# backplane_v1_0.net
KiCad netlist of a schematic drawn in EAGLE
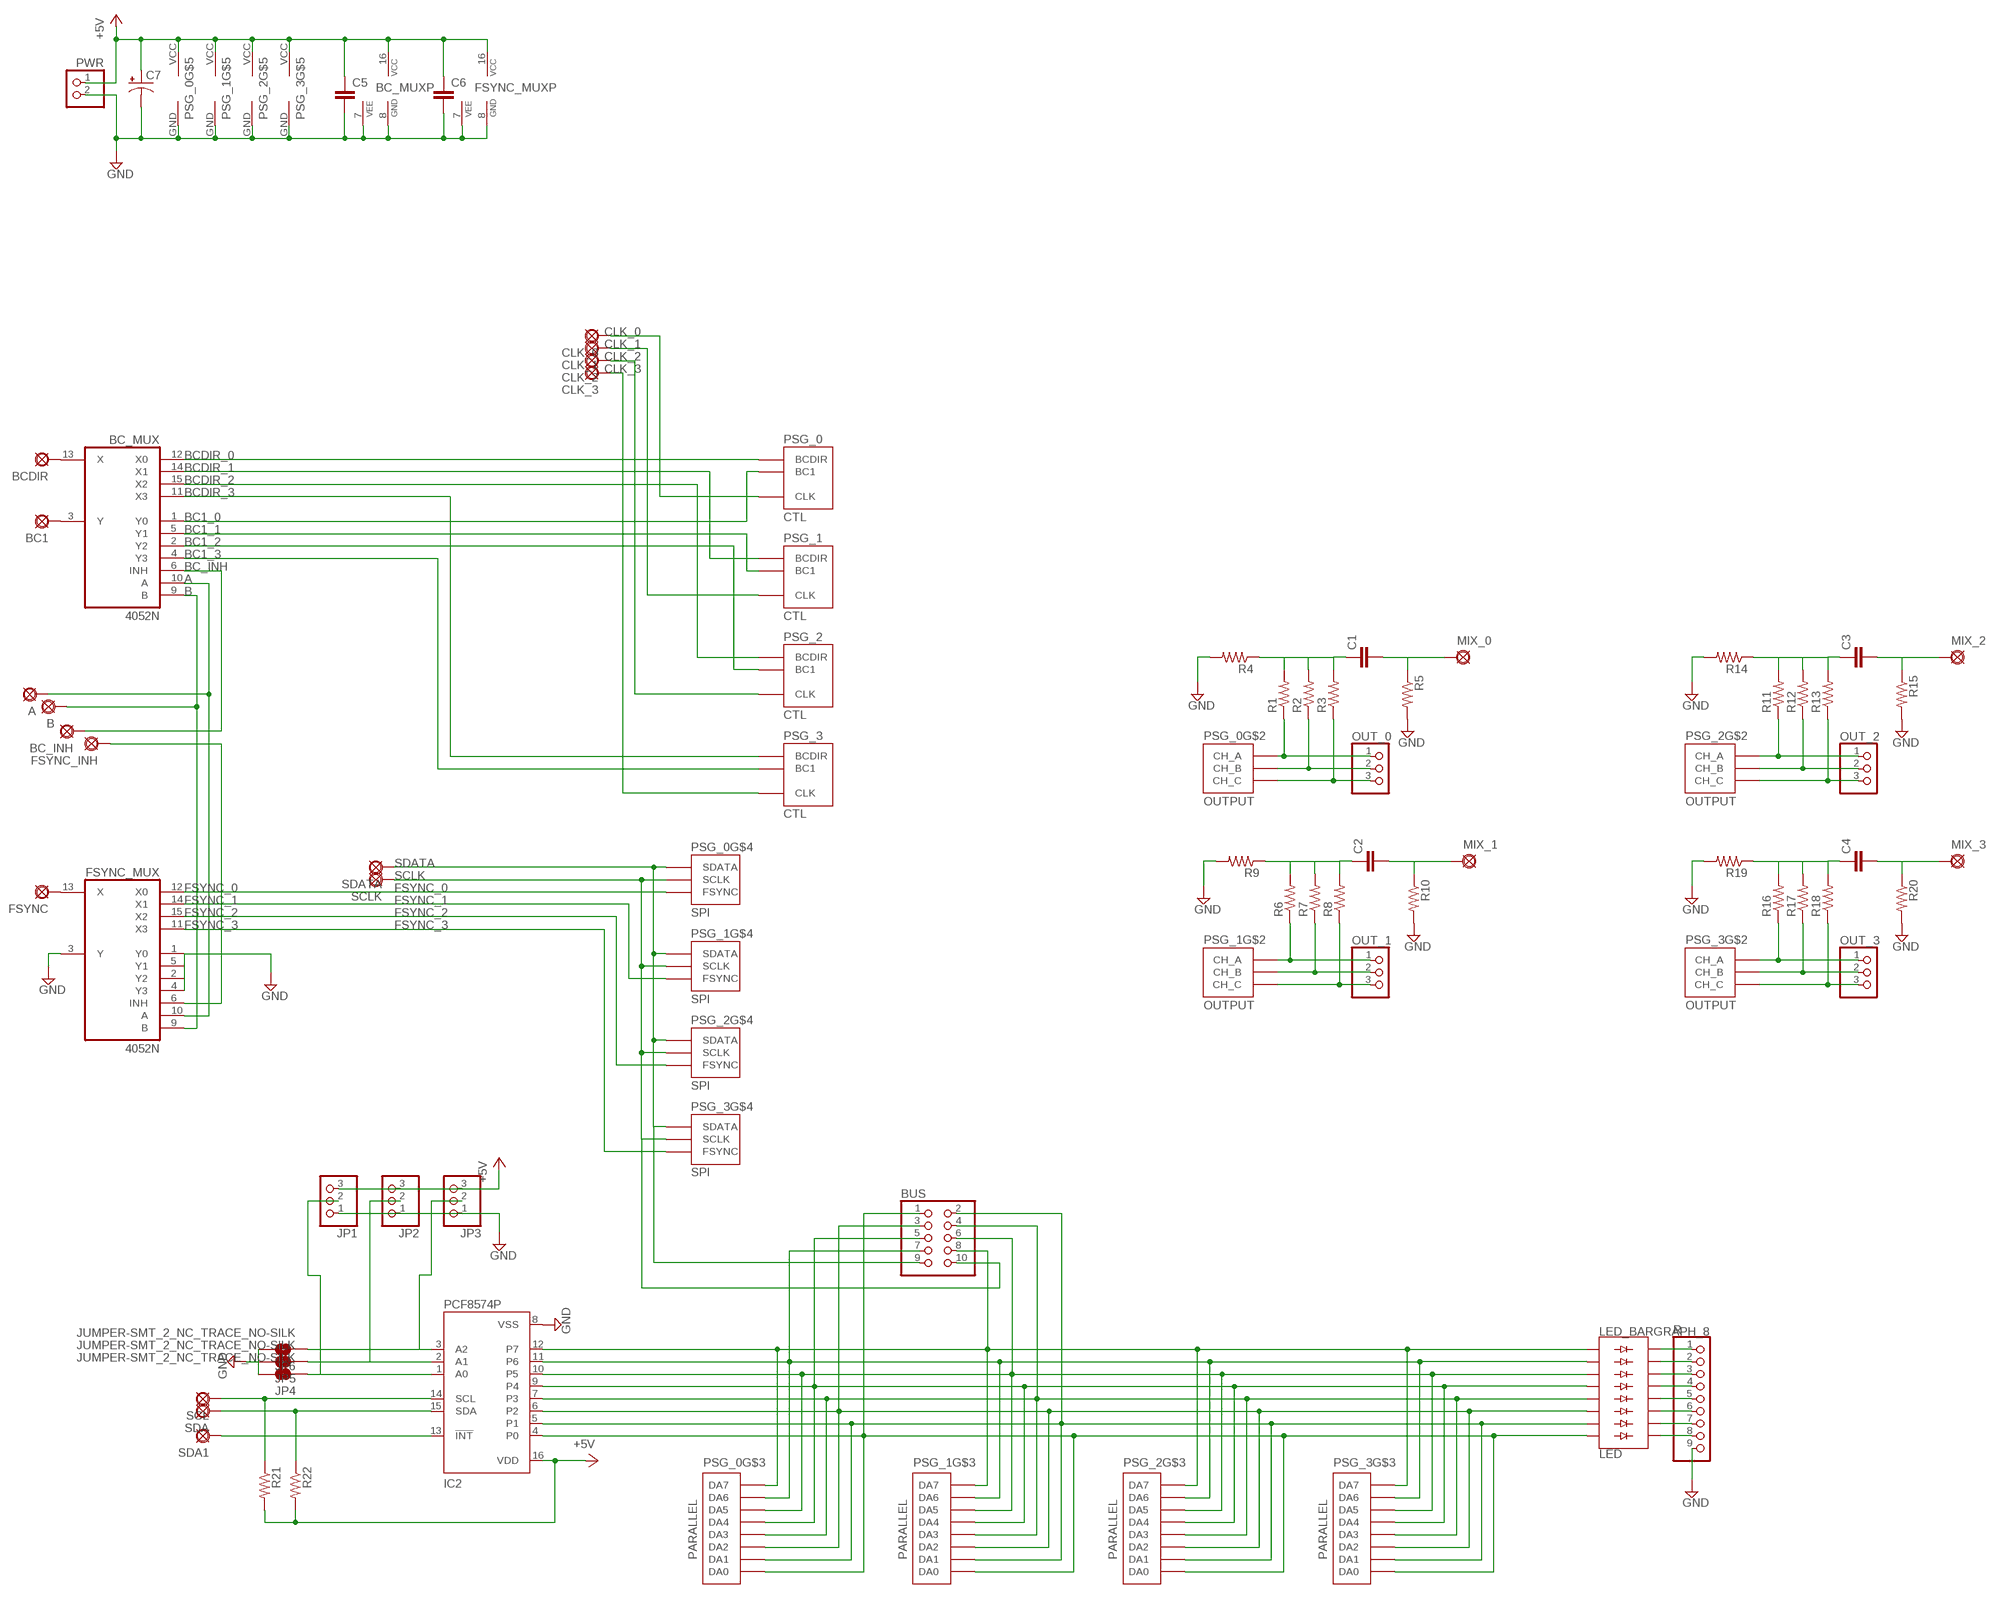
[diagram p0: schematic, sheet 1]

(export (version "E")
  (design (tool "Eeschema 10.0.6"))
  (components
    (comp (ref "A")
      (value "PAD")
      (footprint "eagle-import:SQUARE")
      (libsource (lib "eagle-import") (part "PAD"))
    )
    (comp (ref "B")
      (value "PAD")
      (footprint "eagle-import:SQUARE")
      (libsource (lib "eagle-import") (part "PAD"))
    )
    (comp (ref "BC1")
      (value "PAD")
      (footprint "eagle-import:SQUARE")
      (libsource (lib "eagle-import") (part "PAD"))
    )
    (comp (ref "BCDIR")
      (value "PAD")
      (footprint "eagle-import:SQUARE")
      (libsource (lib "eagle-import") (part "PAD"))
    )
    (comp (ref "BC_INH")
      (value "PAD")
      (footprint "eagle-import:SQUARE")
      (libsource (lib "eagle-import") (part "PAD"))
    )
    (comp (ref "BC_MUX")
      (value "4052N")
      (footprint "eagle-import:DIL16")
      (libsource (lib "eagle-import") (part "4052N"))
    )
    (comp (ref "BUS")
      (value "PINHD-2X5IDC")
      (footprint "eagle-import:10PIN_IDC")
      (libsource (lib "eagle-import") (part "PINHD-2X5IDC"))
    )
    (comp (ref "C1")
      (value "080X0452")
      (footprint "eagle-import:080X045")
      (libsource (lib "eagle-import") (part "080X0452"))
    )
    (comp (ref "C2")
      (value "080X0452")
      (footprint "eagle-import:080X045")
      (libsource (lib "eagle-import") (part "080X0452"))
    )
    (comp (ref "C3")
      (value "080X0452")
      (footprint "eagle-import:080X045")
      (libsource (lib "eagle-import") (part "080X0452"))
    )
    (comp (ref "C4")
      (value "080X0452")
      (footprint "eagle-import:080X045")
      (libsource (lib "eagle-import") (part "080X0452"))
    )
    (comp (ref "C5")
      (value "050X030_0251")
      (footprint "eagle-import:050X030_025")
      (libsource (lib "eagle-import") (part "050X030_0251"))
    )
    (comp (ref "C6")
      (value "050X030_0251")
      (footprint "eagle-import:050X030_025")
      (libsource (lib "eagle-import") (part "050X030_0251"))
    )
    (comp (ref "C7")
      (value "0631")
      (footprint "eagle-import:063_025")
      (libsource (lib "eagle-import") (part "0631"))
    )
    (comp (ref "CLK_0")
      (value "PAD")
      (footprint "eagle-import:SQUARE")
      (libsource (lib "eagle-import") (part "PAD"))
    )
    (comp (ref "CLK_1")
      (value "PAD")
      (footprint "eagle-import:SQUARE")
      (libsource (lib "eagle-import") (part "PAD"))
    )
    (comp (ref "CLK_2")
      (value "PAD")
      (footprint "eagle-import:SQUARE")
      (libsource (lib "eagle-import") (part "PAD"))
    )
    (comp (ref "CLK_3")
      (value "PAD")
      (footprint "eagle-import:SQUARE")
      (libsource (lib "eagle-import") (part "PAD"))
    )
    (comp (ref "FSYNC")
      (value "PAD")
      (footprint "eagle-import:SQUARE")
      (libsource (lib "eagle-import") (part "PAD"))
    )
    (comp (ref "FSYNC_INH")
      (value "PAD")
      (footprint "eagle-import:SQUARE")
      (libsource (lib "eagle-import") (part "PAD"))
    )
    (comp (ref "FSYNC_MUX")
      (value "4052N")
      (footprint "eagle-import:DIL16")
      (libsource (lib "eagle-import") (part "4052N"))
    )
    (comp (ref "IC2")
      (value "PCF8574P")
      (footprint "eagle-import:DIL16")
      (fields (field (name "MPN") "PCF8574PN"))
      (libsource (lib "eagle-import") (part "PCF8574P"))
    )
    (comp (ref "JP1")
      (value "PINHD-1X3")
      (footprint "eagle-import:1X03")
      (libsource (lib "eagle-import") (part "PINHD-1X3"))
    )
    (comp (ref "JP2")
      (value "PINHD-1X3")
      (footprint "eagle-import:1X03")
      (libsource (lib "eagle-import") (part "PINHD-1X3"))
    )
    (comp (ref "JP3")
      (value "PINHD-1X3")
      (footprint "eagle-import:1X03")
      (libsource (lib "eagle-import") (part "PINHD-1X3"))
    )
    (comp (ref "JP4")
      (value "JUMPER-SMT_2_NC_TRACE_NO-SILK")
      (footprint "eagle-import:SMT-JUMPER_2_NC_TRACE_NO-SILK")
      (libsource (lib "eagle-import") (part "JUMPER-SMT_2_NC_TRACE_NO-SILK"))
    )
    (comp (ref "JP5")
      (value "JUMPER-SMT_2_NC_TRACE_NO-SILK")
      (footprint "eagle-import:SMT-JUMPER_2_NC_TRACE_NO-SILK")
      (libsource (lib "eagle-import") (part "JUMPER-SMT_2_NC_TRACE_NO-SILK"))
    )
    (comp (ref "JP6")
      (value "JUMPER-SMT_2_NC_TRACE_NO-SILK")
      (footprint "eagle-import:SMT-JUMPER_2_NC_TRACE_NO-SILK")
      (libsource (lib "eagle-import") (part "JUMPER-SMT_2_NC_TRACE_NO-SILK"))
    )
    (comp (ref "LED")
      (value "LED_BARGRAPH_8")
      (footprint "eagle-import:LED_BARGRAPH_8")
      (libsource (lib "eagle-import") (part "LED_BARGRAPH_8"))
    )
    (comp (ref "MIX_0")
      (value "PAD")
      (footprint "eagle-import:SQUARE")
      (libsource (lib "eagle-import") (part "PAD"))
    )
    (comp (ref "MIX_1")
      (value "PAD")
      (footprint "eagle-import:SQUARE")
      (libsource (lib "eagle-import") (part "PAD"))
    )
    (comp (ref "MIX_2")
      (value "PAD")
      (footprint "eagle-import:SQUARE")
      (libsource (lib "eagle-import") (part "PAD"))
    )
    (comp (ref "MIX_3")
      (value "PAD")
      (footprint "eagle-import:SQUARE")
      (libsource (lib "eagle-import") (part "PAD"))
    )
    (comp (ref "OUT_0")
      (value "PINHD-1X3")
      (footprint "eagle-import:1X03")
      (libsource (lib "eagle-import") (part "PINHD-1X3"))
    )
    (comp (ref "OUT_1")
      (value "PINHD-1X3")
      (footprint "eagle-import:1X03")
      (libsource (lib "eagle-import") (part "PINHD-1X3"))
    )
    (comp (ref "OUT_2")
      (value "PINHD-1X3")
      (footprint "eagle-import:1X03")
      (libsource (lib "eagle-import") (part "PINHD-1X3"))
    )
    (comp (ref "OUT_3")
      (value "PINHD-1X3")
      (footprint "eagle-import:1X03")
      (libsource (lib "eagle-import") (part "PINHD-1X3"))
    )
    (comp (ref "PSG_0")
      (value "PSG_DAUGHTER")
      (footprint "eagle-import:PSG_DAUGHTER")
      (libsource (lib "eagle-import") (part "PSG_DAUGHTER"))
    )
    (comp (ref "PSG_1")
      (value "PSG_DAUGHTER")
      (footprint "eagle-import:PSG_DAUGHTER")
      (libsource (lib "eagle-import") (part "PSG_DAUGHTER"))
    )
    (comp (ref "PSG_2")
      (value "PSG_DAUGHTER")
      (footprint "eagle-import:PSG_DAUGHTER")
      (libsource (lib "eagle-import") (part "PSG_DAUGHTER"))
    )
    (comp (ref "PSG_3")
      (value "PSG_DAUGHTER")
      (footprint "eagle-import:PSG_DAUGHTER")
      (libsource (lib "eagle-import") (part "PSG_DAUGHTER"))
    )
    (comp (ref "PWR")
      (value "PINHD-1X2")
      (footprint "eagle-import:1X02")
      (libsource (lib "eagle-import") (part "PINHD-1X2"))
    )
    (comp (ref "R")
      (value "PINHD-1X9")
      (footprint "eagle-import:1X09")
      (libsource (lib "eagle-import") (part "PINHD-1X9"))
    )
    (comp (ref "R1")
      (value "6MM.3")
      (footprint "eagle-import:R0207_3")
      (libsource (lib "eagle-import") (part "6MM.3"))
    )
    (comp (ref "R2")
      (value "6MM.3")
      (footprint "eagle-import:R0207_3")
      (libsource (lib "eagle-import") (part "6MM.3"))
    )
    (comp (ref "R3")
      (value "6MM.3")
      (footprint "eagle-import:R0207_3")
      (libsource (lib "eagle-import") (part "6MM.3"))
    )
    (comp (ref "R4")
      (value "6MM.3")
      (footprint "eagle-import:R0207_3")
      (libsource (lib "eagle-import") (part "6MM.3"))
    )
    (comp (ref "R5")
      (value "6MM.3")
      (footprint "eagle-import:R0207_3")
      (libsource (lib "eagle-import") (part "6MM.3"))
    )
    (comp (ref "R6")
      (value "6MM.3")
      (footprint "eagle-import:R0207_3")
      (libsource (lib "eagle-import") (part "6MM.3"))
    )
    (comp (ref "R7")
      (value "6MM.3")
      (footprint "eagle-import:R0207_3")
      (libsource (lib "eagle-import") (part "6MM.3"))
    )
    (comp (ref "R8")
      (value "6MM.3")
      (footprint "eagle-import:R0207_3")
      (libsource (lib "eagle-import") (part "6MM.3"))
    )
    (comp (ref "R9")
      (value "6MM.3")
      (footprint "eagle-import:R0207_3")
      (libsource (lib "eagle-import") (part "6MM.3"))
    )
    (comp (ref "R10")
      (value "6MM.3")
      (footprint "eagle-import:R0207_3")
      (libsource (lib "eagle-import") (part "6MM.3"))
    )
    (comp (ref "R11")
      (value "6MM.3")
      (footprint "eagle-import:R0207_3")
      (libsource (lib "eagle-import") (part "6MM.3"))
    )
    (comp (ref "R12")
      (value "6MM.3")
      (footprint "eagle-import:R0207_3")
      (libsource (lib "eagle-import") (part "6MM.3"))
    )
    (comp (ref "R13")
      (value "6MM.3")
      (footprint "eagle-import:R0207_3")
      (libsource (lib "eagle-import") (part "6MM.3"))
    )
    (comp (ref "R14")
      (value "6MM.3")
      (footprint "eagle-import:R0207_3")
      (libsource (lib "eagle-import") (part "6MM.3"))
    )
    (comp (ref "R15")
      (value "6MM.3")
      (footprint "eagle-import:R0207_3")
      (libsource (lib "eagle-import") (part "6MM.3"))
    )
    (comp (ref "R16")
      (value "6MM.3")
      (footprint "eagle-import:R0207_3")
      (libsource (lib "eagle-import") (part "6MM.3"))
    )
    (comp (ref "R17")
      (value "6MM.3")
      (footprint "eagle-import:R0207_3")
      (libsource (lib "eagle-import") (part "6MM.3"))
    )
    (comp (ref "R18")
      (value "6MM.3")
      (footprint "eagle-import:R0207_3")
      (libsource (lib "eagle-import") (part "6MM.3"))
    )
    (comp (ref "R19")
      (value "6MM.3")
      (footprint "eagle-import:R0207_3")
      (libsource (lib "eagle-import") (part "6MM.3"))
    )
    (comp (ref "R20")
      (value "6MM.3")
      (footprint "eagle-import:R0207_3")
      (libsource (lib "eagle-import") (part "6MM.3"))
    )
    (comp (ref "R21")
      (value "6MM.3")
      (footprint "eagle-import:R0207_3")
      (libsource (lib "eagle-import") (part "6MM.3"))
    )
    (comp (ref "R22")
      (value "6MM.3")
      (footprint "eagle-import:R0207_3")
      (libsource (lib "eagle-import") (part "6MM.3"))
    )
    (comp (ref "SCL")
      (value "PAD")
      (footprint "eagle-import:SQUARE")
      (libsource (lib "eagle-import") (part "PAD"))
    )
    (comp (ref "SCLK")
      (value "PAD")
      (footprint "eagle-import:SQUARE")
      (libsource (lib "eagle-import") (part "PAD"))
    )
    (comp (ref "SDA")
      (value "PAD")
      (footprint "eagle-import:SQUARE")
      (libsource (lib "eagle-import") (part "PAD"))
    )
    (comp (ref "SDA1")
      (value "PAD")
      (footprint "eagle-import:SQUARE")
      (libsource (lib "eagle-import") (part "PAD"))
    )
    (comp (ref "SDATA")
      (value "PAD")
      (footprint "eagle-import:SQUARE")
      (libsource (lib "eagle-import") (part "PAD"))
    )
  )
  (nets
    (net (code "1") (name "+5V") (class "Default")
      (node (ref "BC_MUX") (pin "16") (pinfunction "VCC_16") (pintype "power_in"))
      (node (ref "C5") (pin "1") (pinfunction "1_1") (pintype "passive"))
      (node (ref "C6") (pin "1") (pinfunction "1_1") (pintype "passive"))
      (node (ref "C7") (pin "+") (pinfunction "+_+") (pintype "passive"))
      (node (ref "FSYNC_MUX") (pin "16") (pinfunction "VCC_16") (pintype "power_in"))
      (node (ref "IC2") (pin "16") (pinfunction "VDD_16") (pintype "power_in"))
      (node (ref "JP1") (pin "3") (pinfunction "3_3") (pintype "passive"))
      (node (ref "JP2") (pin "3") (pinfunction "3_3") (pintype "passive"))
      (node (ref "JP3") (pin "3") (pinfunction "3_3") (pintype "passive"))
      (node (ref "PSG_0") (pin "VCC") (pinfunction "VCC_VCC") (pintype "power_in"))
      (node (ref "PSG_1") (pin "VCC") (pinfunction "VCC_VCC") (pintype "power_in"))
      (node (ref "PSG_2") (pin "VCC") (pinfunction "VCC_VCC") (pintype "power_in"))
      (node (ref "PSG_3") (pin "VCC") (pinfunction "VCC_VCC") (pintype "power_in"))
      (node (ref "PWR") (pin "1") (pinfunction "1_1") (pintype "passive"))
      (node (ref "R21") (pin "2") (pinfunction "2_2") (pintype "passive"))
      (node (ref "R22") (pin "2") (pinfunction "2_2") (pintype "passive"))
    )
    (net (code "2") (name "/A") (class "Default")
      (node (ref "A") (pin "1") (pinfunction "PAD_1") (pintype "passive"))
      (node (ref "BC_MUX") (pin "10") (pinfunction "A_10") (pintype "input"))
      (node (ref "FSYNC_MUX") (pin "10") (pinfunction "A_10") (pintype "input"))
    )
    (net (code "3") (name "/B") (class "Default")
      (node (ref "B") (pin "1") (pinfunction "PAD_1") (pintype "passive"))
      (node (ref "BC_MUX") (pin "9") (pinfunction "B_9") (pintype "input"))
      (node (ref "FSYNC_MUX") (pin "9") (pinfunction "B_9") (pintype "input"))
    )
    (net (code "4") (name "/BC1_0") (class "Default")
      (node (ref "BC_MUX") (pin "1") (pinfunction "Y0_1") (pintype "bidirectional"))
      (node (ref "PSG_0") (pin "BC1") (pinfunction "BC1_BC1") (pintype "input"))
    )
    (net (code "5") (name "/BC1_1") (class "Default")
      (node (ref "BC_MUX") (pin "5") (pinfunction "Y1_5") (pintype "bidirectional"))
      (node (ref "PSG_1") (pin "BC1") (pinfunction "BC1_BC1") (pintype "input"))
    )
    (net (code "6") (name "/BC1_2") (class "Default")
      (node (ref "BC_MUX") (pin "2") (pinfunction "Y2_2") (pintype "bidirectional"))
      (node (ref "PSG_2") (pin "BC1") (pinfunction "BC1_BC1") (pintype "input"))
    )
    (net (code "7") (name "/BC1_3") (class "Default")
      (node (ref "BC_MUX") (pin "4") (pinfunction "Y3_4") (pintype "bidirectional"))
      (node (ref "PSG_3") (pin "BC1") (pinfunction "BC1_BC1") (pintype "input"))
    )
    (net (code "8") (name "/BCDIR_0") (class "Default")
      (node (ref "BC_MUX") (pin "12") (pinfunction "X0_12") (pintype "bidirectional"))
      (node (ref "PSG_0") (pin "BCDIR") (pinfunction "BCDIR_BCDIR") (pintype "input"))
    )
    (net (code "9") (name "/BCDIR_1") (class "Default")
      (node (ref "BC_MUX") (pin "14") (pinfunction "X1_14") (pintype "bidirectional"))
      (node (ref "PSG_1") (pin "BCDIR") (pinfunction "BCDIR_BCDIR") (pintype "input"))
    )
    (net (code "10") (name "/BCDIR_2") (class "Default")
      (node (ref "BC_MUX") (pin "15") (pinfunction "X2_15") (pintype "bidirectional"))
      (node (ref "PSG_2") (pin "BCDIR") (pinfunction "BCDIR_BCDIR") (pintype "input"))
    )
    (net (code "11") (name "/BCDIR_3") (class "Default")
      (node (ref "BC_MUX") (pin "11") (pinfunction "X3_11") (pintype "bidirectional"))
      (node (ref "PSG_3") (pin "BCDIR") (pinfunction "BCDIR_BCDIR") (pintype "input"))
    )
    (net (code "12") (name "/BC_INH") (class "Default")
      (node (ref "BC_INH") (pin "1") (pinfunction "PAD_1") (pintype "passive"))
      (node (ref "BC_MUX") (pin "6") (pinfunction "INH_6") (pintype "input"))
    )
    (net (code "13") (name "/CLK_0") (class "Default")
      (node (ref "CLK_0") (pin "1") (pinfunction "PAD_1") (pintype "passive"))
      (node (ref "PSG_0") (pin "CLK") (pinfunction "CLK_CLK") (pintype "input"))
    )
    (net (code "14") (name "/CLK_1") (class "Default")
      (node (ref "CLK_1") (pin "1") (pinfunction "PAD_1") (pintype "passive"))
      (node (ref "PSG_1") (pin "CLK") (pinfunction "CLK_CLK") (pintype "input"))
    )
    (net (code "15") (name "/CLK_2") (class "Default")
      (node (ref "CLK_2") (pin "1") (pinfunction "PAD_1") (pintype "passive"))
      (node (ref "PSG_2") (pin "CLK") (pinfunction "CLK_CLK") (pintype "input"))
    )
    (net (code "16") (name "/CLK_3") (class "Default")
      (node (ref "CLK_3") (pin "1") (pinfunction "PAD_1") (pintype "passive"))
      (node (ref "PSG_3") (pin "CLK") (pinfunction "CLK_CLK") (pintype "input"))
    )
    (net (code "17") (name "/FSYNC_0") (class "Default")
      (node (ref "FSYNC_MUX") (pin "12") (pinfunction "X0_12") (pintype "bidirectional"))
      (node (ref "PSG_0") (pin "FSYNC") (pinfunction "FSYNC_FSYNC") (pintype "input"))
    )
    (net (code "18") (name "/FSYNC_1") (class "Default")
      (node (ref "FSYNC_MUX") (pin "14") (pinfunction "X1_14") (pintype "bidirectional"))
      (node (ref "PSG_1") (pin "FSYNC") (pinfunction "FSYNC_FSYNC") (pintype "input"))
    )
    (net (code "19") (name "/FSYNC_2") (class "Default")
      (node (ref "FSYNC_MUX") (pin "15") (pinfunction "X2_15") (pintype "bidirectional"))
      (node (ref "PSG_2") (pin "FSYNC") (pinfunction "FSYNC_FSYNC") (pintype "input"))
    )
    (net (code "20") (name "/FSYNC_3") (class "Default")
      (node (ref "FSYNC_MUX") (pin "11") (pinfunction "X3_11") (pintype "bidirectional"))
      (node (ref "PSG_3") (pin "FSYNC") (pinfunction "FSYNC_FSYNC") (pintype "input"))
    )
    (net (code "21") (name "/SCLK") (class "Default")
      (node (ref "BUS") (pin "10") (pinfunction "10_10") (pintype "passive"))
      (node (ref "PSG_0") (pin "SCLK") (pinfunction "SCLK_SCLK") (pintype "input"))
      (node (ref "PSG_1") (pin "SCLK") (pinfunction "SCLK_SCLK") (pintype "input"))
      (node (ref "PSG_2") (pin "SCLK") (pinfunction "SCLK_SCLK") (pintype "input"))
      (node (ref "PSG_3") (pin "SCLK") (pinfunction "SCLK_SCLK") (pintype "input"))
      (node (ref "SCLK") (pin "1") (pinfunction "PAD_1") (pintype "passive"))
    )
    (net (code "22") (name "/SDATA") (class "Default")
      (node (ref "BUS") (pin "9") (pinfunction "9_9") (pintype "passive"))
      (node (ref "PSG_0") (pin "SDATA") (pinfunction "SDATA_SDATA") (pintype "bidirectional"))
      (node (ref "PSG_1") (pin "SDATA") (pinfunction "SDATA_SDATA") (pintype "bidirectional"))
      (node (ref "PSG_2") (pin "SDATA") (pinfunction "SDATA_SDATA") (pintype "bidirectional"))
      (node (ref "PSG_3") (pin "SDATA") (pinfunction "SDATA_SDATA") (pintype "bidirectional"))
      (node (ref "SDATA") (pin "1") (pinfunction "PAD_1") (pintype "passive"))
    )
    (net (code "23") (name "GND") (class "Default")
      (node (ref "BC_MUX") (pin "7") (pinfunction "VEE_7") (pintype "power_in"))
      (node (ref "BC_MUX") (pin "8") (pinfunction "GND_8") (pintype "power_in"))
      (node (ref "C5") (pin "2") (pinfunction "2_2") (pintype "passive"))
      (node (ref "C6") (pin "2") (pinfunction "2_2") (pintype "passive"))
      (node (ref "C7") (pin "-") (pinfunction "-_-") (pintype "passive"))
      (node (ref "FSYNC_MUX") (pin "1") (pinfunction "Y0_1") (pintype "bidirectional"))
      (node (ref "FSYNC_MUX") (pin "2") (pinfunction "Y2_2") (pintype "bidirectional"))
      (node (ref "FSYNC_MUX") (pin "3") (pinfunction "Y_3") (pintype "bidirectional"))
      (node (ref "FSYNC_MUX") (pin "4") (pinfunction "Y3_4") (pintype "bidirectional"))
      (node (ref "FSYNC_MUX") (pin "5") (pinfunction "Y1_5") (pintype "bidirectional"))
      (node (ref "FSYNC_MUX") (pin "7") (pinfunction "VEE_7") (pintype "power_in"))
      (node (ref "FSYNC_MUX") (pin "8") (pinfunction "GND_8") (pintype "power_in"))
      (node (ref "IC2") (pin "8") (pinfunction "VSS_8") (pintype "power_in"))
      (node (ref "JP1") (pin "1") (pinfunction "1_1") (pintype "passive"))
      (node (ref "JP2") (pin "1") (pinfunction "1_1") (pintype "passive"))
      (node (ref "JP3") (pin "1") (pinfunction "1_1") (pintype "passive"))
      (node (ref "JP4") (pin "2") (pinfunction "2_2") (pintype "passive"))
      (node (ref "JP5") (pin "2") (pinfunction "2_2") (pintype "passive"))
      (node (ref "JP6") (pin "2") (pinfunction "2_2") (pintype "passive"))
      (node (ref "PSG_0") (pin "GND") (pinfunction "GND_GND") (pintype "power_in"))
      (node (ref "PSG_1") (pin "GND") (pinfunction "GND_GND") (pintype "power_in"))
      (node (ref "PSG_2") (pin "GND") (pinfunction "GND_GND") (pintype "power_in"))
      (node (ref "PSG_3") (pin "GND") (pinfunction "GND_GND") (pintype "power_in"))
      (node (ref "PWR") (pin "2") (pinfunction "2_2") (pintype "passive"))
      (node (ref "R") (pin "9") (pinfunction "9_9") (pintype "passive"))
      (node (ref "R10") (pin "2") (pinfunction "2_2") (pintype "passive"))
      (node (ref "R14") (pin "2") (pinfunction "2_2") (pintype "passive"))
      (node (ref "R15") (pin "2") (pinfunction "2_2") (pintype "passive"))
      (node (ref "R19") (pin "2") (pinfunction "2_2") (pintype "passive"))
      (node (ref "R20") (pin "2") (pinfunction "2_2") (pintype "passive"))
      (node (ref "R4") (pin "2") (pinfunction "2_2") (pintype "passive"))
      (node (ref "R5") (pin "2") (pinfunction "2_2") (pintype "passive"))
      (node (ref "R9") (pin "2") (pinfunction "2_2") (pintype "passive"))
    )
    (net (code "24") (name "Net-(BC1-PAD)") (class "Default")
      (node (ref "BC1") (pin "1") (pinfunction "PAD_1") (pintype "passive"))
      (node (ref "BC_MUX") (pin "3") (pinfunction "Y_3") (pintype "bidirectional"))
    )
    (net (code "25") (name "Net-(BCDIR-PAD)") (class "Default")
      (node (ref "BCDIR") (pin "1") (pinfunction "PAD_1") (pintype "passive"))
      (node (ref "BC_MUX") (pin "13") (pinfunction "X_13") (pintype "bidirectional"))
    )
    (net (code "26") (name "Net-(C1-Pad1)") (class "Default")
      (node (ref "C1") (pin "1") (pinfunction "1_1") (pintype "passive"))
      (node (ref "R1") (pin "2") (pinfunction "2_2") (pintype "passive"))
      (node (ref "R2") (pin "2") (pinfunction "2_2") (pintype "passive"))
      (node (ref "R3") (pin "2") (pinfunction "2_2") (pintype "passive"))
      (node (ref "R4") (pin "1") (pinfunction "1_1") (pintype "passive"))
    )
    (net (code "27") (name "Net-(C2-Pad1)") (class "Default")
      (node (ref "C2") (pin "1") (pinfunction "1_1") (pintype "passive"))
      (node (ref "R6") (pin "2") (pinfunction "2_2") (pintype "passive"))
      (node (ref "R7") (pin "2") (pinfunction "2_2") (pintype "passive"))
      (node (ref "R8") (pin "2") (pinfunction "2_2") (pintype "passive"))
      (node (ref "R9") (pin "1") (pinfunction "1_1") (pintype "passive"))
    )
    (net (code "28") (name "Net-(C3-Pad1)") (class "Default")
      (node (ref "C3") (pin "1") (pinfunction "1_1") (pintype "passive"))
      (node (ref "R11") (pin "2") (pinfunction "2_2") (pintype "passive"))
      (node (ref "R12") (pin "2") (pinfunction "2_2") (pintype "passive"))
      (node (ref "R13") (pin "2") (pinfunction "2_2") (pintype "passive"))
      (node (ref "R14") (pin "1") (pinfunction "1_1") (pintype "passive"))
    )
    (net (code "29") (name "Net-(C4-Pad1)") (class "Default")
      (node (ref "C4") (pin "1") (pinfunction "1_1") (pintype "passive"))
      (node (ref "R16") (pin "2") (pinfunction "2_2") (pintype "passive"))
      (node (ref "R17") (pin "2") (pinfunction "2_2") (pintype "passive"))
      (node (ref "R18") (pin "2") (pinfunction "2_2") (pintype "passive"))
      (node (ref "R19") (pin "1") (pinfunction "1_1") (pintype "passive"))
    )
    (net (code "30") (name "Net-(FSYNC-PAD)") (class "Default")
      (node (ref "FSYNC") (pin "1") (pinfunction "PAD_1") (pintype "passive"))
      (node (ref "FSYNC_MUX") (pin "13") (pinfunction "X_13") (pintype "bidirectional"))
    )
    (net (code "31") (name "Net-(FSYNC_INH-PAD)") (class "Default")
      (node (ref "FSYNC_INH") (pin "1") (pinfunction "PAD_1") (pintype "passive"))
      (node (ref "FSYNC_MUX") (pin "6") (pinfunction "INH_6") (pintype "input"))
    )
    (net (code "32") (name "Net-(IC2-A0)") (class "Default")
      (node (ref "IC2") (pin "1") (pinfunction "A0_1") (pintype "input"))
      (node (ref "JP1") (pin "2") (pinfunction "2_2") (pintype "passive"))
      (node (ref "JP4") (pin "1") (pinfunction "1_1") (pintype "passive"))
    )
    (net (code "33") (name "Net-(IC2-A1)") (class "Default")
      (node (ref "IC2") (pin "2") (pinfunction "A1_2") (pintype "input"))
      (node (ref "JP2") (pin "2") (pinfunction "2_2") (pintype "passive"))
      (node (ref "JP5") (pin "1") (pinfunction "1_1") (pintype "passive"))
    )
    (net (code "34") (name "Net-(IC2-A2)") (class "Default")
      (node (ref "IC2") (pin "3") (pinfunction "A2_3") (pintype "input"))
      (node (ref "JP3") (pin "2") (pinfunction "2_2") (pintype "passive"))
      (node (ref "JP6") (pin "1") (pinfunction "1_1") (pintype "passive"))
    )
    (net (code "35") (name "Net-(IC2-P0)") (class "Default")
      (node (ref "BUS") (pin "1") (pinfunction "1_1") (pintype "passive"))
      (node (ref "IC2") (pin "4") (pinfunction "P0_4") (pintype "bidirectional"))
      (node (ref "LED") (pin "A0") (pinfunction "A0_A0") (pintype "passive"))
      (node (ref "PSG_0") (pin "DA0") (pinfunction "DA0_DA0") (pintype "bidirectional"))
      (node (ref "PSG_1") (pin "DA0") (pinfunction "DA0_DA0") (pintype "bidirectional"))
      (node (ref "PSG_2") (pin "DA0") (pinfunction "DA0_DA0") (pintype "bidirectional"))
      (node (ref "PSG_3") (pin "DA0") (pinfunction "DA0_DA0") (pintype "bidirectional"))
    )
    (net (code "36") (name "Net-(IC2-P1)") (class "Default")
      (node (ref "BUS") (pin "2") (pinfunction "2_2") (pintype "passive"))
      (node (ref "IC2") (pin "5") (pinfunction "P1_5") (pintype "bidirectional"))
      (node (ref "LED") (pin "A1") (pinfunction "A1_A1") (pintype "passive"))
      (node (ref "PSG_0") (pin "DA1") (pinfunction "DA1_DA1") (pintype "bidirectional"))
      (node (ref "PSG_1") (pin "DA1") (pinfunction "DA1_DA1") (pintype "bidirectional"))
      (node (ref "PSG_2") (pin "DA1") (pinfunction "DA1_DA1") (pintype "bidirectional"))
      (node (ref "PSG_3") (pin "DA1") (pinfunction "DA1_DA1") (pintype "bidirectional"))
    )
    (net (code "37") (name "Net-(IC2-P2)") (class "Default")
      (node (ref "BUS") (pin "3") (pinfunction "3_3") (pintype "passive"))
      (node (ref "IC2") (pin "6") (pinfunction "P2_6") (pintype "bidirectional"))
      (node (ref "LED") (pin "A2") (pinfunction "A2_A2") (pintype "passive"))
      (node (ref "PSG_0") (pin "DA2") (pinfunction "DA2_DA2") (pintype "bidirectional"))
      (node (ref "PSG_1") (pin "DA2") (pinfunction "DA2_DA2") (pintype "bidirectional"))
      (node (ref "PSG_2") (pin "DA2") (pinfunction "DA2_DA2") (pintype "bidirectional"))
      (node (ref "PSG_3") (pin "DA2") (pinfunction "DA2_DA2") (pintype "bidirectional"))
    )
    (net (code "38") (name "Net-(IC2-P3)") (class "Default")
      (node (ref "BUS") (pin "4") (pinfunction "4_4") (pintype "passive"))
      (node (ref "IC2") (pin "7") (pinfunction "P3_7") (pintype "bidirectional"))
      (node (ref "LED") (pin "A3") (pinfunction "A3_A3") (pintype "passive"))
      (node (ref "PSG_0") (pin "DA3") (pinfunction "DA3_DA3") (pintype "bidirectional"))
      (node (ref "PSG_1") (pin "DA3") (pinfunction "DA3_DA3") (pintype "bidirectional"))
      (node (ref "PSG_2") (pin "DA3") (pinfunction "DA3_DA3") (pintype "bidirectional"))
      (node (ref "PSG_3") (pin "DA3") (pinfunction "DA3_DA3") (pintype "bidirectional"))
    )
    (net (code "39") (name "Net-(IC2-P4)") (class "Default")
      (node (ref "BUS") (pin "5") (pinfunction "5_5") (pintype "passive"))
      (node (ref "IC2") (pin "9") (pinfunction "P4_9") (pintype "bidirectional"))
      (node (ref "LED") (pin "A4") (pinfunction "A4_A4") (pintype "passive"))
      (node (ref "PSG_0") (pin "DA4") (pinfunction "DA4_DA4") (pintype "bidirectional"))
      (node (ref "PSG_1") (pin "DA4") (pinfunction "DA4_DA4") (pintype "bidirectional"))
      (node (ref "PSG_2") (pin "DA4") (pinfunction "DA4_DA4") (pintype "bidirectional"))
      (node (ref "PSG_3") (pin "DA4") (pinfunction "DA4_DA4") (pintype "bidirectional"))
    )
    (net (code "40") (name "Net-(IC2-P5)") (class "Default")
      (node (ref "BUS") (pin "6") (pinfunction "6_6") (pintype "passive"))
      (node (ref "IC2") (pin "10") (pinfunction "P5_10") (pintype "bidirectional"))
      (node (ref "LED") (pin "A5") (pinfunction "A5_A5") (pintype "passive"))
      (node (ref "PSG_0") (pin "DA5") (pinfunction "DA5_DA5") (pintype "bidirectional"))
      (node (ref "PSG_1") (pin "DA5") (pinfunction "DA5_DA5") (pintype "bidirectional"))
      (node (ref "PSG_2") (pin "DA5") (pinfunction "DA5_DA5") (pintype "bidirectional"))
      (node (ref "PSG_3") (pin "DA5") (pinfunction "DA5_DA5") (pintype "bidirectional"))
    )
    (net (code "41") (name "Net-(IC2-P6)") (class "Default")
      (node (ref "BUS") (pin "7") (pinfunction "7_7") (pintype "passive"))
      (node (ref "IC2") (pin "11") (pinfunction "P6_11") (pintype "bidirectional"))
      (node (ref "LED") (pin "A6") (pinfunction "A6_A6") (pintype "passive"))
      (node (ref "PSG_0") (pin "DA6") (pinfunction "DA6_DA6") (pintype "bidirectional"))
      (node (ref "PSG_1") (pin "DA6") (pinfunction "DA6_DA6") (pintype "bidirectional"))
      (node (ref "PSG_2") (pin "DA6") (pinfunction "DA6_DA6") (pintype "bidirectional"))
      (node (ref "PSG_3") (pin "DA6") (pinfunction "DA6_DA6") (pintype "bidirectional"))
    )
    (net (code "42") (name "Net-(IC2-P7)") (class "Default")
      (node (ref "BUS") (pin "8") (pinfunction "8_8") (pintype "passive"))
      (node (ref "IC2") (pin "12") (pinfunction "P7_12") (pintype "bidirectional"))
      (node (ref "LED") (pin "A7") (pinfunction "A7_A7") (pintype "passive"))
      (node (ref "PSG_0") (pin "DA7") (pinfunction "DA7_DA7") (pintype "bidirectional"))
      (node (ref "PSG_1") (pin "DA7") (pinfunction "DA7_DA7") (pintype "bidirectional"))
      (node (ref "PSG_2") (pin "DA7") (pinfunction "DA7_DA7") (pintype "bidirectional"))
      (node (ref "PSG_3") (pin "DA7") (pinfunction "DA7_DA7") (pintype "bidirectional"))
    )
    (net (code "43") (name "Net-(IC2-SCL)") (class "Default")
      (node (ref "IC2") (pin "14") (pinfunction "SCL_14") (pintype "input"))
      (node (ref "R21") (pin "1") (pinfunction "1_1") (pintype "passive"))
      (node (ref "SCL") (pin "1") (pinfunction "PAD_1") (pintype "passive"))
    )
    (net (code "44") (name "Net-(IC2-SDA)") (class "Default")
      (node (ref "IC2") (pin "15") (pinfunction "SDA_15") (pintype "bidirectional"))
      (node (ref "R22") (pin "1") (pinfunction "1_1") (pintype "passive"))
      (node (ref "SDA") (pin "1") (pinfunction "PAD_1") (pintype "passive"))
    )
    (net (code "45") (name "Net-(IC2-~{INT})") (class "Default")
      (node (ref "IC2") (pin "13") (pinfunction "~{INT}_13") (pintype "output"))
      (node (ref "SDA1") (pin "1") (pinfunction "PAD_1") (pintype "passive"))
    )
    (net (code "46") (name "Net-(LED-PadC0)") (class "Default")
      (node (ref "LED") (pin "C0") (pinfunction "C0_C0") (pintype "passive"))
      (node (ref "R") (pin "8") (pinfunction "8_8") (pintype "passive"))
    )
    (net (code "47") (name "Net-(LED-PadC1)") (class "Default")
      (node (ref "LED") (pin "C1") (pinfunction "C1_C1") (pintype "passive"))
      (node (ref "R") (pin "7") (pinfunction "7_7") (pintype "passive"))
    )
    (net (code "48") (name "Net-(LED-PadC2)") (class "Default")
      (node (ref "LED") (pin "C2") (pinfunction "C2_C2") (pintype "passive"))
      (node (ref "R") (pin "6") (pinfunction "6_6") (pintype "passive"))
    )
    (net (code "49") (name "Net-(LED-PadC3)") (class "Default")
      (node (ref "LED") (pin "C3") (pinfunction "C3_C3") (pintype "passive"))
      (node (ref "R") (pin "5") (pinfunction "5_5") (pintype "passive"))
    )
    (net (code "50") (name "Net-(LED-PadC4)") (class "Default")
      (node (ref "LED") (pin "C4") (pinfunction "C4_C4") (pintype "passive"))
      (node (ref "R") (pin "4") (pinfunction "4_4") (pintype "passive"))
    )
    (net (code "51") (name "Net-(LED-PadC5)") (class "Default")
      (node (ref "LED") (pin "C5") (pinfunction "C5_C5") (pintype "passive"))
      (node (ref "R") (pin "3") (pinfunction "3_3") (pintype "passive"))
    )
    (net (code "52") (name "Net-(LED-PadC6)") (class "Default")
      (node (ref "LED") (pin "C6") (pinfunction "C6_C6") (pintype "passive"))
      (node (ref "R") (pin "2") (pinfunction "2_2") (pintype "passive"))
    )
    (net (code "53") (name "Net-(LED-PadC7)") (class "Default")
      (node (ref "LED") (pin "C7") (pinfunction "C7_C7") (pintype "passive"))
      (node (ref "R") (pin "1") (pinfunction "1_1") (pintype "passive"))
    )
    (net (code "54") (name "Net-(MIX_0-PAD)") (class "Default")
      (node (ref "C1") (pin "2") (pinfunction "2_2") (pintype "passive"))
      (node (ref "MIX_0") (pin "1") (pinfunction "PAD_1") (pintype "passive"))
      (node (ref "R5") (pin "1") (pinfunction "1_1") (pintype "passive"))
    )
    (net (code "55") (name "Net-(MIX_1-PAD)") (class "Default")
      (node (ref "C2") (pin "2") (pinfunction "2_2") (pintype "passive"))
      (node (ref "MIX_1") (pin "1") (pinfunction "PAD_1") (pintype "passive"))
      (node (ref "R10") (pin "1") (pinfunction "1_1") (pintype "passive"))
    )
    (net (code "56") (name "Net-(MIX_2-PAD)") (class "Default")
      (node (ref "C3") (pin "2") (pinfunction "2_2") (pintype "passive"))
      (node (ref "MIX_2") (pin "1") (pinfunction "PAD_1") (pintype "passive"))
      (node (ref "R15") (pin "1") (pinfunction "1_1") (pintype "passive"))
    )
    (net (code "57") (name "Net-(MIX_3-PAD)") (class "Default")
      (node (ref "C4") (pin "2") (pinfunction "2_2") (pintype "passive"))
      (node (ref "MIX_3") (pin "1") (pinfunction "PAD_1") (pintype "passive"))
      (node (ref "R20") (pin "1") (pinfunction "1_1") (pintype "passive"))
    )
    (net (code "58") (name "Net-(PSG_0B-CH_A)") (class "Default")
      (node (ref "OUT_0") (pin "1") (pinfunction "1_1") (pintype "passive"))
      (node (ref "PSG_0") (pin "OUT_A") (pinfunction "CH_A_OUT_A") (pintype "input"))
      (node (ref "R1") (pin "1") (pinfunction "1_1") (pintype "passive"))
    )
    (net (code "59") (name "Net-(PSG_0B-CH_B)") (class "Default")
      (node (ref "OUT_0") (pin "2") (pinfunction "2_2") (pintype "passive"))
      (node (ref "PSG_0") (pin "OUT_B") (pinfunction "CH_B_OUT_B") (pintype "input"))
      (node (ref "R2") (pin "1") (pinfunction "1_1") (pintype "passive"))
    )
    (net (code "60") (name "Net-(PSG_0B-CH_C)") (class "Default")
      (node (ref "OUT_0") (pin "3") (pinfunction "3_3") (pintype "passive"))
      (node (ref "PSG_0") (pin "OUT_C") (pinfunction "CH_C_OUT_C") (pintype "input"))
      (node (ref "R3") (pin "1") (pinfunction "1_1") (pintype "passive"))
    )
    (net (code "61") (name "Net-(PSG_1B-CH_A)") (class "Default")
      (node (ref "OUT_1") (pin "1") (pinfunction "1_1") (pintype "passive"))
      (node (ref "PSG_1") (pin "OUT_A") (pinfunction "CH_A_OUT_A") (pintype "input"))
      (node (ref "R6") (pin "1") (pinfunction "1_1") (pintype "passive"))
    )
    (net (code "62") (name "Net-(PSG_1B-CH_B)") (class "Default")
      (node (ref "OUT_1") (pin "2") (pinfunction "2_2") (pintype "passive"))
      (node (ref "PSG_1") (pin "OUT_B") (pinfunction "CH_B_OUT_B") (pintype "input"))
      (node (ref "R7") (pin "1") (pinfunction "1_1") (pintype "passive"))
    )
    (net (code "63") (name "Net-(PSG_1B-CH_C)") (class "Default")
      (node (ref "OUT_1") (pin "3") (pinfunction "3_3") (pintype "passive"))
      (node (ref "PSG_1") (pin "OUT_C") (pinfunction "CH_C_OUT_C") (pintype "input"))
      (node (ref "R8") (pin "1") (pinfunction "1_1") (pintype "passive"))
    )
    (net (code "64") (name "Net-(PSG_2B-CH_A)") (class "Default")
      (node (ref "OUT_2") (pin "1") (pinfunction "1_1") (pintype "passive"))
      (node (ref "PSG_2") (pin "OUT_A") (pinfunction "CH_A_OUT_A") (pintype "input"))
      (node (ref "R11") (pin "1") (pinfunction "1_1") (pintype "passive"))
    )
    (net (code "65") (name "Net-(PSG_2B-CH_B)") (class "Default")
      (node (ref "OUT_2") (pin "2") (pinfunction "2_2") (pintype "passive"))
      (node (ref "PSG_2") (pin "OUT_B") (pinfunction "CH_B_OUT_B") (pintype "input"))
      (node (ref "R12") (pin "1") (pinfunction "1_1") (pintype "passive"))
    )
    (net (code "66") (name "Net-(PSG_2B-CH_C)") (class "Default")
      (node (ref "OUT_2") (pin "3") (pinfunction "3_3") (pintype "passive"))
      (node (ref "PSG_2") (pin "OUT_C") (pinfunction "CH_C_OUT_C") (pintype "input"))
      (node (ref "R13") (pin "1") (pinfunction "1_1") (pintype "passive"))
    )
    (net (code "67") (name "Net-(PSG_3B-CH_A)") (class "Default")
      (node (ref "OUT_3") (pin "1") (pinfunction "1_1") (pintype "passive"))
      (node (ref "PSG_3") (pin "OUT_A") (pinfunction "CH_A_OUT_A") (pintype "input"))
      (node (ref "R16") (pin "1") (pinfunction "1_1") (pintype "passive"))
    )
    (net (code "68") (name "Net-(PSG_3B-CH_B)") (class "Default")
      (node (ref "OUT_3") (pin "2") (pinfunction "2_2") (pintype "passive"))
      (node (ref "PSG_3") (pin "OUT_B") (pinfunction "CH_B_OUT_B") (pintype "input"))
      (node (ref "R17") (pin "1") (pinfunction "1_1") (pintype "passive"))
    )
    (net (code "69") (name "Net-(PSG_3B-CH_C)") (class "Default")
      (node (ref "OUT_3") (pin "3") (pinfunction "3_3") (pintype "passive"))
      (node (ref "PSG_3") (pin "OUT_C") (pinfunction "CH_C_OUT_C") (pintype "input"))
      (node (ref "R18") (pin "1") (pinfunction "1_1") (pintype "passive"))
    )
  )
)
